# LCD.net
KiCad netlist of a schematic drawn in Altium Designer
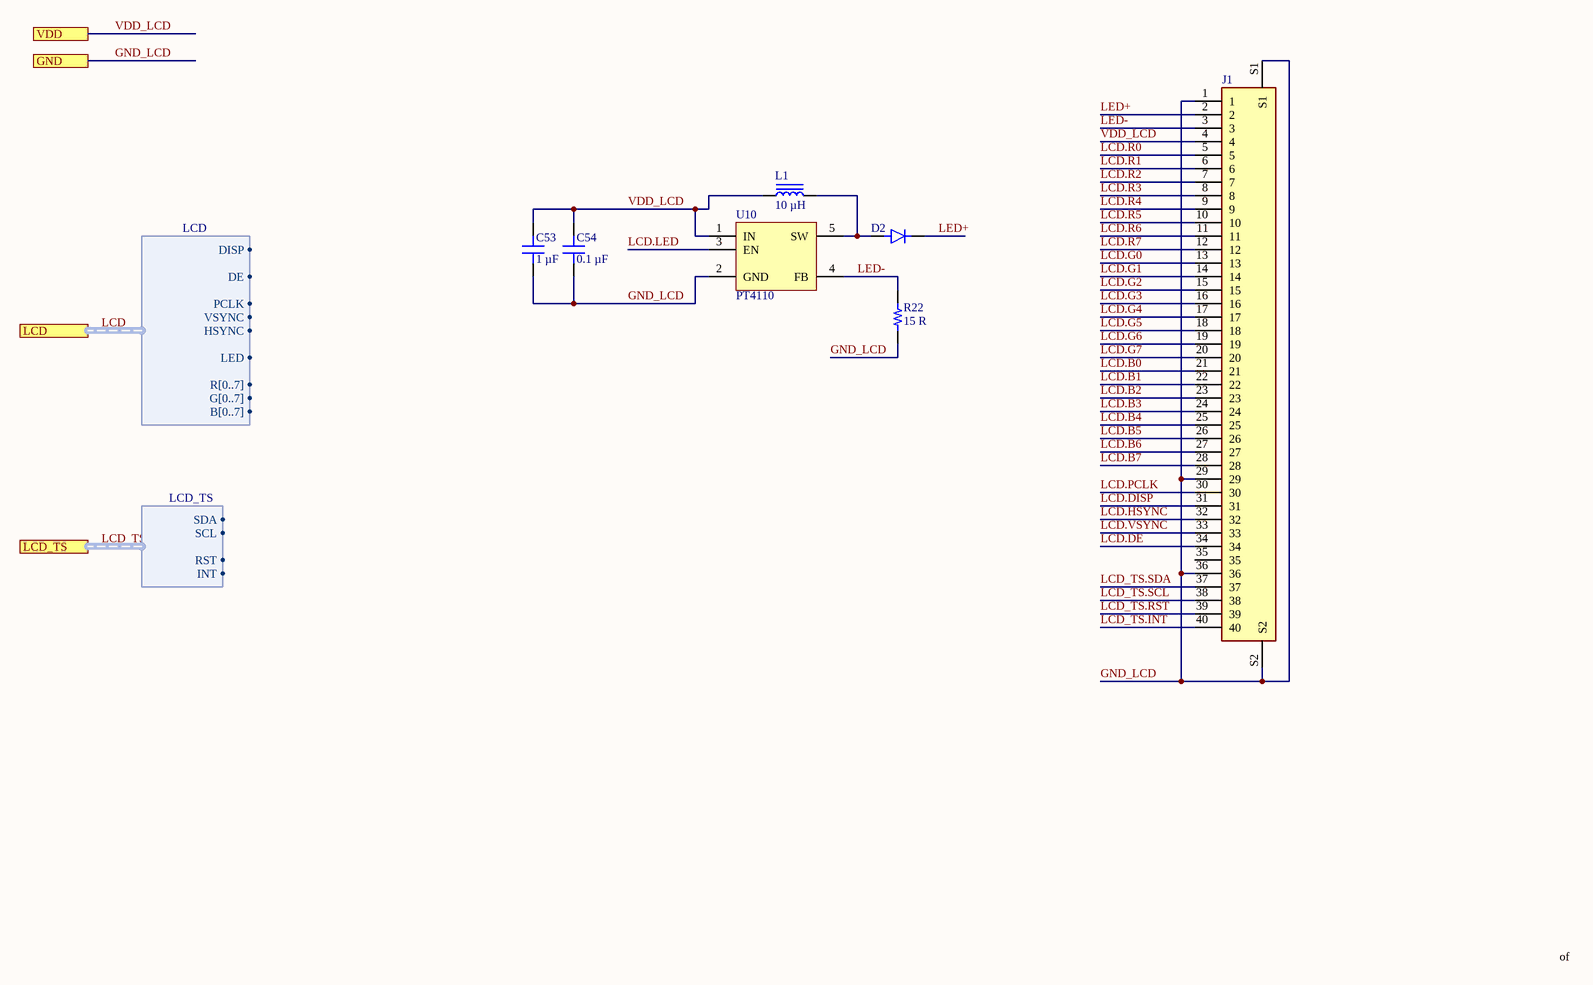
[diagram p0: LCD.SchDoc]

(export (version "E")
  (design (tool "Eeschema 10.0.6"))
  (components
    (comp (ref "C53")
      (value "1 µF")
      (footprint "CAP 0402_1005")
      (description "CAP CER 0.1UF 16V X7R 0402")
      (fields (field (name "PART NUMBER") "C0402C104K4RACAUTO") (field (name "MANUFACTURER") "KEMET"))
      (libsource (lib "Celestial Altium Library - altium_library") (part "Capacitor"))
    )
    (comp (ref "C54")
      (value "0.1 µF")
      (footprint "CAP 0402_1005")
      (description "CAP CER 0.1UF 16V X7R 0402")
      (fields (field (name "PART NUMBER") "C0402C104K4RACAUTO") (field (name "MANUFACTURER") "KEMET"))
      (libsource (lib "Celestial Altium Library - altium_library") (part "Capacitor"))
    )
    (comp (ref "D2")
      (value "Diode")
      (footprint "Diode DFN1608D-2 (SOD1608)")
      (description "DFN1608D-2 (SOD1608)")
      (fields (field (name "MANUFACTURER") "Cree") (field (name "MOUSER PART NUMBER") "941-CLV1LFKBC7673673"))
      (libsource (lib "IC") (part "Diode"))
    )
    (comp (ref "J1")
      (value "40pin_0.5mm_ZIF")
      (footprint "40pin_0.5mmPitch")
      (description "40 Position FFC, FPC Connector Contacts, Top 0.020 _0.50mm_ Surface Mount, Right Angle")
      (fields (field (name "MP") "FH12A-40S-0.5SH_55_") (field (name "MF") "Hirose"))
      (libsource (lib "IC") (part "40pin_0.5mm_ZIF"))
    )
    (comp (ref "L1")
      (value "10 µH")
      (footprint "IND 0806_2016")
      (description "FIXED IND 10UH 600MA 875MOHM SMD")
      (fields
        (field (name "PART NUMBER") "TYA201610100M-10")
        (field (name "MANUFACTURER") "Laird-Signal Integrity Products")
      )
      (libsource (lib "Celestial Altium Library - altium_library") (part "Inductor"))
    )
    (comp (ref "R22")
      (value "15 R")
      (footprint "RES 0603_1608")
      (description "RES 10K OHM 0.1% 1/16W 0603")
      (fields
        (field (name "PART NUMBER") "RNCS0603BKE10K0")
        (field (name "MANUFACTURER") "Stackpole Electronics Inc")
      )
      (libsource (lib "Celestial Altium Library - altium_library") (part "Resistor"))
    )
    (comp (ref "U10")
      (value "PT4110")
      (footprint "SOT-89-5")
      (description "LED Backlight Driver")
      (libsource (lib "IC") (part "PT4110"))
    )
  )
  (nets
    (net (code "3") (name "/GND_LCD") (class "Default")
      (node (ref "C53") (pin "1") (pinfunction "1_1") (pintype "passive"))
      (node (ref "C54") (pin "1") (pinfunction "1_1") (pintype "passive"))
      (node (ref "J1") (pin "1") (pinfunction "1_1") (pintype "passive"))
      (node (ref "J1") (pin "29") (pinfunction "29_29") (pintype "passive"))
      (node (ref "J1") (pin "36") (pinfunction "36_36") (pintype "passive"))
      (node (ref "J1") (pin "S1") (pinfunction "S1_S1") (pintype "passive"))
      (node (ref "J1") (pin "S2") (pinfunction "S2_S2") (pintype "passive"))
      (node (ref "R22") (pin "2") (pinfunction "2_2") (pintype "passive"))
      (node (ref "U10") (pin "2") (pinfunction "GND_2") (pintype "passive"))
    )
    (net (code "4") (name "/LCD.B0") (class "Default")
      (node (ref "J1") (pin "21") (pinfunction "21_21") (pintype "passive"))
    )
    (net (code "5") (name "/LCD.B1") (class "Default")
      (node (ref "J1") (pin "22") (pinfunction "22_22") (pintype "passive"))
    )
    (net (code "6") (name "/LCD.B2") (class "Default")
      (node (ref "J1") (pin "23") (pinfunction "23_23") (pintype "passive"))
    )
    (net (code "7") (name "/LCD.B3") (class "Default")
      (node (ref "J1") (pin "24") (pinfunction "24_24") (pintype "passive"))
    )
    (net (code "8") (name "/LCD.B4") (class "Default")
      (node (ref "J1") (pin "25") (pinfunction "25_25") (pintype "passive"))
    )
    (net (code "9") (name "/LCD.B5") (class "Default")
      (node (ref "J1") (pin "26") (pinfunction "26_26") (pintype "passive"))
    )
    (net (code "10") (name "/LCD.B6") (class "Default")
      (node (ref "J1") (pin "27") (pinfunction "27_27") (pintype "passive"))
    )
    (net (code "11") (name "/LCD.B7") (class "Default")
      (node (ref "J1") (pin "28") (pinfunction "28_28") (pintype "passive"))
    )
    (net (code "12") (name "/LCD.DE") (class "Default")
      (node (ref "J1") (pin "34") (pinfunction "34_34") (pintype "passive"))
    )
    (net (code "13") (name "/LCD.DISP") (class "Default")
      (node (ref "J1") (pin "31") (pinfunction "31_31") (pintype "passive"))
    )
    (net (code "14") (name "/LCD.G0") (class "Default")
      (node (ref "J1") (pin "13") (pinfunction "13_13") (pintype "passive"))
    )
    (net (code "15") (name "/LCD.G1") (class "Default")
      (node (ref "J1") (pin "14") (pinfunction "14_14") (pintype "passive"))
    )
    (net (code "16") (name "/LCD.G2") (class "Default")
      (node (ref "J1") (pin "15") (pinfunction "15_15") (pintype "passive"))
    )
    (net (code "17") (name "/LCD.G3") (class "Default")
      (node (ref "J1") (pin "16") (pinfunction "16_16") (pintype "passive"))
    )
    (net (code "18") (name "/LCD.G4") (class "Default")
      (node (ref "J1") (pin "17") (pinfunction "17_17") (pintype "passive"))
    )
    (net (code "19") (name "/LCD.G5") (class "Default")
      (node (ref "J1") (pin "18") (pinfunction "18_18") (pintype "passive"))
    )
    (net (code "20") (name "/LCD.G6") (class "Default")
      (node (ref "J1") (pin "19") (pinfunction "19_19") (pintype "passive"))
    )
    (net (code "21") (name "/LCD.G7") (class "Default")
      (node (ref "J1") (pin "20") (pinfunction "20_20") (pintype "passive"))
    )
    (net (code "22") (name "/LCD.HSYNC") (class "Default")
      (node (ref "J1") (pin "32") (pinfunction "32_32") (pintype "passive"))
    )
    (net (code "23") (name "/LCD.LED") (class "Default")
      (node (ref "U10") (pin "3") (pinfunction "EN_3") (pintype "passive"))
    )
    (net (code "24") (name "/LCD.PCLK") (class "Default")
      (node (ref "J1") (pin "30") (pinfunction "30_30") (pintype "passive"))
    )
    (net (code "25") (name "/LCD.R0") (class "Default")
      (node (ref "J1") (pin "5") (pinfunction "5_5") (pintype "passive"))
    )
    (net (code "26") (name "/LCD.R1") (class "Default")
      (node (ref "J1") (pin "6") (pinfunction "6_6") (pintype "passive"))
    )
    (net (code "27") (name "/LCD.R2") (class "Default")
      (node (ref "J1") (pin "7") (pinfunction "7_7") (pintype "passive"))
    )
    (net (code "28") (name "/LCD.R3") (class "Default")
      (node (ref "J1") (pin "8") (pinfunction "8_8") (pintype "passive"))
    )
    (net (code "29") (name "/LCD.R4") (class "Default")
      (node (ref "J1") (pin "9") (pinfunction "9_9") (pintype "passive"))
    )
    (net (code "30") (name "/LCD.R5") (class "Default")
      (node (ref "J1") (pin "10") (pinfunction "10_10") (pintype "passive"))
    )
    (net (code "31") (name "/LCD.R6") (class "Default")
      (node (ref "J1") (pin "11") (pinfunction "11_11") (pintype "passive"))
    )
    (net (code "32") (name "/LCD.R7") (class "Default")
      (node (ref "J1") (pin "12") (pinfunction "12_12") (pintype "passive"))
    )
    (net (code "33") (name "/LCD.VSYNC") (class "Default")
      (node (ref "J1") (pin "33") (pinfunction "33_33") (pintype "passive"))
    )
    (net (code "34") (name "/LCD_TS.INT") (class "Default")
      (node (ref "J1") (pin "40") (pinfunction "40_40") (pintype "passive"))
    )
    (net (code "35") (name "/LCD_TS.RST") (class "Default")
      (node (ref "J1") (pin "39") (pinfunction "39_39") (pintype "passive"))
    )
    (net (code "36") (name "/LCD_TS.SCL") (class "Default")
      (node (ref "J1") (pin "38") (pinfunction "38_38") (pintype "passive"))
    )
    (net (code "37") (name "/LCD_TS.SDA") (class "Default")
      (node (ref "J1") (pin "37") (pinfunction "37_37") (pintype "passive"))
    )
    (net (code "40") (name "/LED+") (class "Default")
      (node (ref "D2") (pin "1") (pinfunction "A_1") (pintype "passive"))
      (node (ref "J1") (pin "2") (pinfunction "2_2") (pintype "passive"))
    )
    (net (code "41") (name "/LED-") (class "Default")
      (node (ref "J1") (pin "3") (pinfunction "3_3") (pintype "passive"))
      (node (ref "R22") (pin "1") (pinfunction "1_1") (pintype "passive"))
      (node (ref "U10") (pin "4") (pinfunction "FB_4") (pintype "passive"))
    )
    (net (code "42") (name "/VDD_LCD") (class "Default")
      (node (ref "C53") (pin "2") (pinfunction "2_2") (pintype "passive"))
      (node (ref "C54") (pin "2") (pinfunction "2_2") (pintype "passive"))
      (node (ref "J1") (pin "4") (pinfunction "4_4") (pintype "passive"))
      (node (ref "L1") (pin "1") (pinfunction "1_1") (pintype "passive"))
      (node (ref "U10") (pin "1") (pinfunction "IN_1") (pintype "passive"))
    )
    (net (code "43") (name "Net-(D2-BLUE(C))") (class "Default")
      (node (ref "D2") (pin "2") (pinfunction "BLUE(C)_2") (pintype "passive"))
      (node (ref "L1") (pin "2") (pinfunction "2_2") (pintype "passive"))
      (node (ref "U10") (pin "5") (pinfunction "SW_5") (pintype "passive"))
    )
    (net (code "44") (name "unconnected-(J1-Pad35)") (class "Default")
      (node (ref "J1") (pin "35") (pinfunction "35_35") (pintype "passive"))
    )
  )
)
